# satshakit-nero.net
KiCad netlist of a schematic drawn in EAGLE
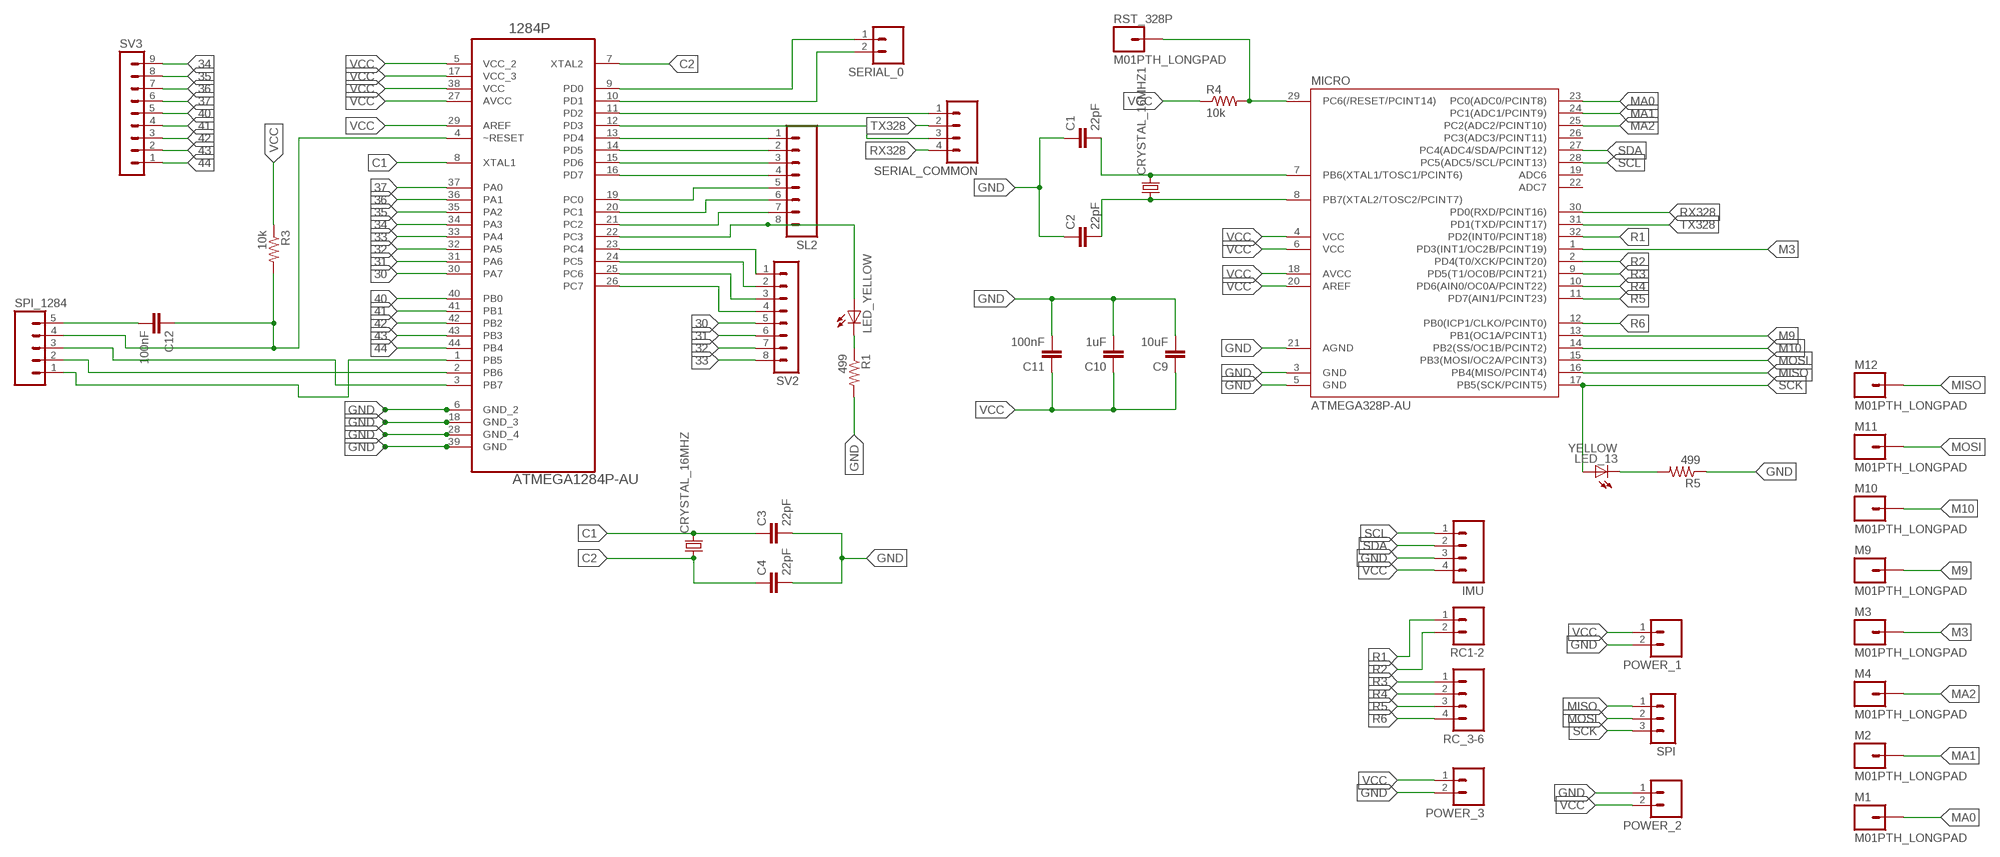
[diagram p0: schematic, sheet 1]

(export (version "E")
  (design (tool "Eeschema 10.0.6"))
  (components
    (comp (ref "1284P")
      (value "ATMEGA1284P-AU")
      (footprint "eagle-import:QFP80P1200X1200X120-44N")
      (libsource (lib "eagle-import") (part "ATMEGA1284P-AU"))
    )
    (comp (ref "C1")
      (value "22pF")
      (footprint "eagle-import:1206")
      (libsource (lib "eagle-import") (part "CAP1206"))
    )
    (comp (ref "C2")
      (value "22pF")
      (footprint "eagle-import:1206")
      (libsource (lib "eagle-import") (part "CAP1206"))
    )
    (comp (ref "C3")
      (value "22pF")
      (footprint "eagle-import:1206")
      (libsource (lib "eagle-import") (part "CAP1206"))
    )
    (comp (ref "C4")
      (value "22pF")
      (footprint "eagle-import:1206")
      (libsource (lib "eagle-import") (part "CAP1206"))
    )
    (comp (ref "C9")
      (value "10uF")
      (footprint "eagle-import:1206")
      (libsource (lib "eagle-import") (part "CAP1206"))
    )
    (comp (ref "C10")
      (value "1uF")
      (footprint "eagle-import:1206")
      (libsource (lib "eagle-import") (part "CAP1206"))
    )
    (comp (ref "C11")
      (value "100nF")
      (footprint "eagle-import:1206")
      (libsource (lib "eagle-import") (part "CAP1206"))
    )
    (comp (ref "C12")
      (value "100nF")
      (footprint "eagle-import:1206")
      (libsource (lib "eagle-import") (part "CAP1206"))
    )
    (comp (ref "CRYSTAL_16MHZ")
      (value "CRYSTALHC49UP")
      (footprint "eagle-import:HC49UP")
      (libsource (lib "eagle-import") (part "CRYSTALHC49UP"))
    )
    (comp (ref "CRYSTAL_16MHZ1")
      (value "CRYSTALHC49UP")
      (footprint "eagle-import:HC49UP")
      (libsource (lib "eagle-import") (part "CRYSTALHC49UP"))
    )
    (comp (ref "IMU")
      (value "M04")
      (footprint "eagle-import:04P")
      (libsource (lib "eagle-import") (part "M04"))
    )
    (comp (ref "LED_13")
      (value "YELLOW")
      (footprint "eagle-import:1206")
      (libsource (lib "eagle-import") (part "LED1206"))
    )
    (comp (ref "LED_YELLOW")
      (value "LED1206")
      (footprint "eagle-import:1206")
      (libsource (lib "eagle-import") (part "FAB_Hello_LED1206"))
    )
    (comp (ref "M1")
      (value "M01PTH_LONGPAD")
      (footprint "eagle-import:1X01_LONGPAD")
      (libsource (lib "eagle-import") (part "M01PTH_LONGPAD"))
    )
    (comp (ref "M2")
      (value "M01PTH_LONGPAD")
      (footprint "eagle-import:1X01_LONGPAD")
      (libsource (lib "eagle-import") (part "M01PTH_LONGPAD"))
    )
    (comp (ref "M3")
      (value "M01PTH_LONGPAD")
      (footprint "eagle-import:1X01_LONGPAD")
      (libsource (lib "eagle-import") (part "M01PTH_LONGPAD"))
    )
    (comp (ref "M4")
      (value "M01PTH_LONGPAD")
      (footprint "eagle-import:1X01_LONGPAD")
      (libsource (lib "eagle-import") (part "M01PTH_LONGPAD"))
    )
    (comp (ref "M9")
      (value "M01PTH_LONGPAD")
      (footprint "eagle-import:1X01_LONGPAD")
      (libsource (lib "eagle-import") (part "M01PTH_LONGPAD"))
    )
    (comp (ref "M10")
      (value "M01PTH_LONGPAD")
      (footprint "eagle-import:1X01_LONGPAD")
      (libsource (lib "eagle-import") (part "M01PTH_LONGPAD"))
    )
    (comp (ref "M11")
      (value "M01PTH_LONGPAD")
      (footprint "eagle-import:1X01_LONGPAD")
      (libsource (lib "eagle-import") (part "M01PTH_LONGPAD"))
    )
    (comp (ref "M12")
      (value "M01PTH_LONGPAD")
      (footprint "eagle-import:1X01_LONGPAD")
      (libsource (lib "eagle-import") (part "M01PTH_LONGPAD"))
    )
    (comp (ref "MICRO")
      (value "ATMEGA328P-AU")
      (footprint "eagle-import:TQFP32-08")
      (libsource (lib "eagle-import") (part "ATMEGA48/88/168-AU"))
    )
    (comp (ref "POWER_1")
      (value "M02")
      (footprint "eagle-import:02P")
      (libsource (lib "eagle-import") (part "M02"))
    )
    (comp (ref "POWER_2")
      (value "M02")
      (footprint "eagle-import:02P")
      (libsource (lib "eagle-import") (part "M02"))
    )
    (comp (ref "POWER_3")
      (value "M02")
      (footprint "eagle-import:02P")
      (libsource (lib "eagle-import") (part "M02"))
    )
    (comp (ref "R1")
      (value "499")
      (footprint "eagle-import:R1206")
      (libsource (lib "eagle-import") (part "RES-US1206"))
    )
    (comp (ref "R3")
      (value "10k")
      (footprint "eagle-import:R1206")
      (libsource (lib "eagle-import") (part "RES-US1206"))
    )
    (comp (ref "R4")
      (value "10k")
      (footprint "eagle-import:1206")
      (libsource (lib "eagle-import") (part "RESISTOR1206"))
    )
    (comp (ref "R5")
      (value "499")
      (footprint "eagle-import:1206")
      (libsource (lib "eagle-import") (part "RESISTOR1206"))
    )
    (comp (ref "RC1-2")
      (value "M02")
      (footprint "eagle-import:02P")
      (libsource (lib "eagle-import") (part "M02"))
    )
    (comp (ref "RC_3-6")
      (value "M04LONGPADS")
      (footprint "eagle-import:1X04_LONGPADS")
      (libsource (lib "eagle-import") (part "M04LONGPADS"))
    )
    (comp (ref "RST_328P")
      (value "M01PTH_LONGPAD")
      (footprint "eagle-import:1X01_LONGPAD")
      (libsource (lib "eagle-import") (part "M01PTH_LONGPAD"))
    )
    (comp (ref "SERIAL_0")
      (value "M02")
      (footprint "eagle-import:02P")
      (libsource (lib "eagle-import") (part "M02"))
    )
    (comp (ref "SERIAL_COMMON")
      (value "M04")
      (footprint "eagle-import:04P")
      (libsource (lib "eagle-import") (part "M04"))
    )
    (comp (ref "SL2")
      (value "M08")
      (footprint "eagle-import:08P")
      (libsource (lib "eagle-import") (part "M08"))
    )
    (comp (ref "SPI")
      (value "MA03-1")
      (footprint "eagle-import:MA03-1")
      (libsource (lib "eagle-import") (part "MA03-1"))
    )
    (comp (ref "SPI_1284")
      (value "M05")
      (footprint "eagle-import:05P")
      (libsource (lib "eagle-import") (part "M05"))
    )
    (comp (ref "SV2")
      (value "MA08-1")
      (footprint "eagle-import:MA08-1")
      (libsource (lib "eagle-import") (part "MA08-1"))
    )
    (comp (ref "SV3")
      (value "MA09-1")
      (footprint "eagle-import:MA09-1")
      (libsource (lib "eagle-import") (part "MA09-1"))
    )
  )
  (nets
    (net (code "1") (name "30") (class "Default")
      (node (ref "1284P") (pin "30") (pinfunction "PA7_30") (pintype "bidirectional"))
      (node (ref "SV2") (pin "5") (pinfunction "5_5") (pintype "passive"))
    )
    (net (code "2") (name "31") (class "Default")
      (node (ref "1284P") (pin "31") (pinfunction "PA6_31") (pintype "bidirectional"))
      (node (ref "SV2") (pin "6") (pinfunction "6_6") (pintype "passive"))
    )
    (net (code "3") (name "32") (class "Default")
      (node (ref "1284P") (pin "32") (pinfunction "PA5_32") (pintype "bidirectional"))
      (node (ref "SV2") (pin "7") (pinfunction "7_7") (pintype "passive"))
    )
    (net (code "4") (name "33") (class "Default")
      (node (ref "1284P") (pin "33") (pinfunction "PA4_33") (pintype "bidirectional"))
      (node (ref "SV2") (pin "8") (pinfunction "8_8") (pintype "passive"))
    )
    (net (code "5") (name "34") (class "Default")
      (node (ref "1284P") (pin "34") (pinfunction "PA3_34") (pintype "bidirectional"))
      (node (ref "SV3") (pin "9") (pinfunction "9_9") (pintype "passive"))
    )
    (net (code "6") (name "35") (class "Default")
      (node (ref "1284P") (pin "35") (pinfunction "PA2_35") (pintype "bidirectional"))
      (node (ref "SV3") (pin "8") (pinfunction "8_8") (pintype "passive"))
    )
    (net (code "7") (name "36") (class "Default")
      (node (ref "1284P") (pin "36") (pinfunction "PA1_36") (pintype "bidirectional"))
      (node (ref "SV3") (pin "7") (pinfunction "7_7") (pintype "passive"))
    )
    (net (code "8") (name "37") (class "Default")
      (node (ref "1284P") (pin "37") (pinfunction "PA0_37") (pintype "bidirectional"))
      (node (ref "SV3") (pin "6") (pinfunction "6_6") (pintype "passive"))
    )
    (net (code "9") (name "40") (class "Default")
      (node (ref "1284P") (pin "40") (pinfunction "PB0_40") (pintype "bidirectional"))
      (node (ref "SV3") (pin "5") (pinfunction "5_5") (pintype "passive"))
    )
    (net (code "10") (name "41") (class "Default")
      (node (ref "1284P") (pin "41") (pinfunction "PB1_41") (pintype "bidirectional"))
      (node (ref "SV3") (pin "4") (pinfunction "4_4") (pintype "passive"))
    )
    (net (code "11") (name "42") (class "Default")
      (node (ref "1284P") (pin "42") (pinfunction "PB2_42") (pintype "bidirectional"))
      (node (ref "SV3") (pin "3") (pinfunction "3_3") (pintype "passive"))
    )
    (net (code "12") (name "43") (class "Default")
      (node (ref "1284P") (pin "43") (pinfunction "PB3_43") (pintype "bidirectional"))
      (node (ref "SV3") (pin "2") (pinfunction "2_2") (pintype "passive"))
    )
    (net (code "13") (name "44") (class "Default")
      (node (ref "1284P") (pin "44") (pinfunction "PB4_44") (pintype "bidirectional"))
      (node (ref "SV3") (pin "1") (pinfunction "1_1") (pintype "passive"))
    )
    (net (code "14") (name "C1") (class "Default")
      (node (ref "1284P") (pin "8") (pinfunction "XTAL1_8") (pintype "input"))
      (node (ref "C3") (pin "1") (pinfunction "1_1") (pintype "passive"))
      (node (ref "CRYSTAL_16MHZ") (pin "2") (pinfunction "2_2") (pintype "passive"))
    )
    (net (code "15") (name "C2") (class "Default")
      (node (ref "1284P") (pin "7") (pinfunction "XTAL2_7") (pintype "output"))
      (node (ref "C4") (pin "1") (pinfunction "1_1") (pintype "passive"))
      (node (ref "CRYSTAL_16MHZ") (pin "1") (pinfunction "1_1") (pintype "passive"))
    )
    (net (code "16") (name "GND") (class "Default")
      (node (ref "1284P") (pin "6") (pinfunction "GND_2_6") (pintype "passive"))
      (node (ref "C1") (pin "1") (pinfunction "1_1") (pintype "passive"))
      (node (ref "C10") (pin "2") (pinfunction "2_2") (pintype "passive"))
      (node (ref "C11") (pin "2") (pinfunction "2_2") (pintype "passive"))
      (node (ref "C2") (pin "1") (pinfunction "1_1") (pintype "passive"))
      (node (ref "C3") (pin "2") (pinfunction "2_2") (pintype "passive"))
      (node (ref "C4") (pin "2") (pinfunction "2_2") (pintype "passive"))
      (node (ref "C9") (pin "2") (pinfunction "2_2") (pintype "passive"))
      (node (ref "IMU") (pin "3") (pinfunction "3_3") (pintype "passive"))
      (node (ref "MICRO") (pin "21") (pinfunction "AGND_21") (pintype "power_in"))
      (node (ref "MICRO") (pin "3") (pinfunction "GND_3") (pintype "power_in"))
      (node (ref "MICRO") (pin "5") (pinfunction "GND_5") (pintype "power_in"))
      (node (ref "POWER_1") (pin "2") (pinfunction "2_2") (pintype "passive"))
      (node (ref "POWER_2") (pin "1") (pinfunction "1_1") (pintype "passive"))
      (node (ref "POWER_3") (pin "2") (pinfunction "2_2") (pintype "passive"))
      (node (ref "R1") (pin "2") (pinfunction "2_2") (pintype "passive"))
      (node (ref "R5") (pin "1") (pinfunction "1_1") (pintype "passive"))
    )
    (net (code "17") (name "M3") (class "Default")
      (node (ref "M3") (pin "1") (pinfunction "1_1") (pintype "passive"))
      (node (ref "MICRO") (pin "1") (pinfunction "PD3(INT1/OC2B/PCINT19)_1") (pintype "bidirectional"))
    )
    (net (code "18") (name "M9") (class "Default")
      (node (ref "M9") (pin "1") (pinfunction "1_1") (pintype "passive"))
      (node (ref "MICRO") (pin "13") (pinfunction "PB1(OC1A/PCINT1)_13") (pintype "bidirectional"))
    )
    (net (code "19") (name "M10") (class "Default")
      (node (ref "M10") (pin "1") (pinfunction "1_1") (pintype "passive"))
      (node (ref "MICRO") (pin "14") (pinfunction "PB2(SS/OC1B/PCINT2)_14") (pintype "bidirectional"))
    )
    (net (code "20") (name "MA0") (class "Default")
      (node (ref "M1") (pin "1") (pinfunction "1_1") (pintype "passive"))
      (node (ref "MICRO") (pin "23") (pinfunction "PC0(ADC0/PCINT8)_23") (pintype "bidirectional"))
    )
    (net (code "21") (name "MA1") (class "Default")
      (node (ref "M2") (pin "1") (pinfunction "1_1") (pintype "passive"))
      (node (ref "MICRO") (pin "24") (pinfunction "PC1(ADC1/PCINT9)_24") (pintype "bidirectional"))
    )
    (net (code "22") (name "MA2") (class "Default")
      (node (ref "M4") (pin "1") (pinfunction "1_1") (pintype "passive"))
      (node (ref "MICRO") (pin "25") (pinfunction "PC2(ADC2/PCINT10)_25") (pintype "bidirectional"))
    )
    (net (code "23") (name "MISO") (class "Default")
      (node (ref "M12") (pin "1") (pinfunction "1_1") (pintype "passive"))
      (node (ref "MICRO") (pin "16") (pinfunction "PB4(MISO/PCINT4)_16") (pintype "bidirectional"))
      (node (ref "SPI") (pin "1") (pinfunction "1_1") (pintype "passive"))
    )
    (net (code "24") (name "MOSI") (class "Default")
      (node (ref "M11") (pin "1") (pinfunction "1_1") (pintype "passive"))
      (node (ref "MICRO") (pin "15") (pinfunction "PB3(MOSI/OC2A/PCINT3)_15") (pintype "bidirectional"))
      (node (ref "SPI") (pin "2") (pinfunction "2_2") (pintype "passive"))
    )
    (net (code "25") (name "Net-(1284P-PB5)") (class "Default")
      (node (ref "1284P") (pin "1") (pinfunction "PB5_1") (pintype "bidirectional"))
      (node (ref "SPI_1284") (pin "1") (pinfunction "1_1") (pintype "passive"))
    )
    (net (code "26") (name "Net-(1284P-PB6)") (class "Default")
      (node (ref "1284P") (pin "2") (pinfunction "PB6_2") (pintype "bidirectional"))
      (node (ref "SPI_1284") (pin "2") (pinfunction "2_2") (pintype "passive"))
    )
    (net (code "27") (name "Net-(1284P-PB7)") (class "Default")
      (node (ref "1284P") (pin "3") (pinfunction "PB7_3") (pintype "bidirectional"))
      (node (ref "SPI_1284") (pin "3") (pinfunction "3_3") (pintype "passive"))
    )
    (net (code "28") (name "Net-(1284P-PC0)") (class "Default")
      (node (ref "1284P") (pin "19") (pinfunction "PC0_19") (pintype "bidirectional"))
      (node (ref "SL2") (pin "5") (pinfunction "5_5") (pintype "passive"))
    )
    (net (code "29") (name "Net-(1284P-PC1)") (class "Default")
      (node (ref "1284P") (pin "20") (pinfunction "PC1_20") (pintype "bidirectional"))
      (node (ref "SL2") (pin "6") (pinfunction "6_6") (pintype "passive"))
    )
    (net (code "30") (name "Net-(1284P-PC2)") (class "Default")
      (node (ref "1284P") (pin "21") (pinfunction "PC2_21") (pintype "bidirectional"))
      (node (ref "SL2") (pin "7") (pinfunction "7_7") (pintype "passive"))
    )
    (net (code "31") (name "Net-(1284P-PC3)") (class "Default")
      (node (ref "1284P") (pin "22") (pinfunction "PC3_22") (pintype "bidirectional"))
      (node (ref "LED_YELLOW") (pin "1") (pinfunction "A_1") (pintype "passive"))
      (node (ref "SL2") (pin "8") (pinfunction "8_8") (pintype "passive"))
    )
    (net (code "32") (name "Net-(1284P-PC4)") (class "Default")
      (node (ref "1284P") (pin "23") (pinfunction "PC4_23") (pintype "bidirectional"))
      (node (ref "SV2") (pin "1") (pinfunction "1_1") (pintype "passive"))
    )
    (net (code "33") (name "Net-(1284P-PC5)") (class "Default")
      (node (ref "1284P") (pin "24") (pinfunction "PC5_24") (pintype "bidirectional"))
      (node (ref "SV2") (pin "2") (pinfunction "2_2") (pintype "passive"))
    )
    (net (code "34") (name "Net-(1284P-PC6)") (class "Default")
      (node (ref "1284P") (pin "25") (pinfunction "PC6_25") (pintype "bidirectional"))
      (node (ref "SV2") (pin "3") (pinfunction "3_3") (pintype "passive"))
    )
    (net (code "35") (name "Net-(1284P-PC7)") (class "Default")
      (node (ref "1284P") (pin "26") (pinfunction "PC7_26") (pintype "bidirectional"))
      (node (ref "SV2") (pin "4") (pinfunction "4_4") (pintype "passive"))
    )
    (net (code "36") (name "Net-(1284P-PD0)") (class "Default")
      (node (ref "1284P") (pin "9") (pinfunction "PD0_9") (pintype "bidirectional"))
      (node (ref "SERIAL_0") (pin "1") (pinfunction "1_1") (pintype "passive"))
    )
    (net (code "37") (name "Net-(1284P-PD1)") (class "Default")
      (node (ref "1284P") (pin "10") (pinfunction "PD1_10") (pintype "bidirectional"))
      (node (ref "SERIAL_0") (pin "2") (pinfunction "2_2") (pintype "passive"))
    )
    (net (code "38") (name "Net-(1284P-PD2)") (class "Default")
      (node (ref "1284P") (pin "11") (pinfunction "PD2_11") (pintype "bidirectional"))
      (node (ref "SERIAL_COMMON") (pin "1") (pinfunction "1_1") (pintype "passive"))
    )
    (net (code "39") (name "Net-(1284P-PD3)") (class "Default")
      (node (ref "1284P") (pin "12") (pinfunction "PD3_12") (pintype "bidirectional"))
      (node (ref "SERIAL_COMMON") (pin "3") (pinfunction "3_3") (pintype "passive"))
    )
    (net (code "40") (name "Net-(1284P-PD4)") (class "Default")
      (node (ref "1284P") (pin "13") (pinfunction "PD4_13") (pintype "bidirectional"))
      (node (ref "SL2") (pin "1") (pinfunction "1_1") (pintype "passive"))
    )
    (net (code "41") (name "Net-(1284P-PD5)") (class "Default")
      (node (ref "1284P") (pin "14") (pinfunction "PD5_14") (pintype "bidirectional"))
      (node (ref "SL2") (pin "2") (pinfunction "2_2") (pintype "passive"))
    )
    (net (code "42") (name "Net-(1284P-PD6)") (class "Default")
      (node (ref "1284P") (pin "15") (pinfunction "PD6_15") (pintype "bidirectional"))
      (node (ref "SL2") (pin "3") (pinfunction "3_3") (pintype "passive"))
    )
    (net (code "43") (name "Net-(1284P-PD7)") (class "Default")
      (node (ref "1284P") (pin "16") (pinfunction "PD7_16") (pintype "bidirectional"))
      (node (ref "SL2") (pin "4") (pinfunction "4_4") (pintype "passive"))
    )
    (net (code "44") (name "Net-(1284P-~{RESET})") (class "Default")
      (node (ref "1284P") (pin "4") (pinfunction "~{RESET}_4") (pintype "input"))
      (node (ref "C12") (pin "1") (pinfunction "1_1") (pintype "passive"))
      (node (ref "R3") (pin "2") (pinfunction "2_2") (pintype "passive"))
      (node (ref "SPI_1284") (pin "4") (pinfunction "4_4") (pintype "passive"))
    )
    (net (code "45") (name "Net-(C12-Pad2)") (class "Default")
      (node (ref "C12") (pin "2") (pinfunction "2_2") (pintype "passive"))
      (node (ref "SPI_1284") (pin "5") (pinfunction "5_5") (pintype "passive"))
    )
    (net (code "46") (name "Net-(LED_13-C)") (class "Default")
      (node (ref "LED_13") (pin "2") (pinfunction "C_2") (pintype "passive"))
      (node (ref "R5") (pin "2") (pinfunction "2_2") (pintype "passive"))
    )
    (net (code "47") (name "Net-(LED_YELLOW-C)") (class "Default")
      (node (ref "LED_YELLOW") (pin "2") (pinfunction "C_2") (pintype "passive"))
      (node (ref "R1") (pin "1") (pinfunction "1_1") (pintype "passive"))
    )
    (net (code "48") (name "Net-(MICRO-PB6(XTAL1{slash}TOSC1{slash}PCINT6))") (class "Default")
      (node (ref "C1") (pin "2") (pinfunction "2_2") (pintype "passive"))
      (node (ref "CRYSTAL_16MHZ1") (pin "2") (pinfunction "2_2") (pintype "passive"))
      (node (ref "MICRO") (pin "7") (pinfunction "PB6(XTAL1/TOSC1/PCINT6)_7") (pintype "bidirectional"))
    )
    (net (code "49") (name "Net-(MICRO-PB7(XTAL2{slash}TOSC2{slash}PCINT7))") (class "Default")
      (node (ref "C2") (pin "2") (pinfunction "2_2") (pintype "passive"))
      (node (ref "CRYSTAL_16MHZ1") (pin "1") (pinfunction "1_1") (pintype "passive"))
      (node (ref "MICRO") (pin "8") (pinfunction "PB7(XTAL2/TOSC2/PCINT7)_8") (pintype "bidirectional"))
    )
    (net (code "50") (name "Net-(MICRO-PC6({slash}RESET{slash}PCINT14))") (class "Default")
      (node (ref "MICRO") (pin "29") (pinfunction "PC6(/RESET/PCINT14)_29") (pintype "bidirectional"))
      (node (ref "R4") (pin "2") (pinfunction "2_2") (pintype "passive"))
      (node (ref "RST_328P") (pin "1") (pinfunction "1_1") (pintype "passive"))
    )
    (net (code "51") (name "R1") (class "Default")
      (node (ref "MICRO") (pin "32") (pinfunction "PD2(INT0/PCINT18)_32") (pintype "bidirectional"))
      (node (ref "RC1-2") (pin "1") (pinfunction "1_1") (pintype "passive"))
    )
    (net (code "52") (name "R2") (class "Default")
      (node (ref "MICRO") (pin "2") (pinfunction "PD4(T0/XCK/PCINT20)_2") (pintype "bidirectional"))
      (node (ref "RC1-2") (pin "2") (pinfunction "2_2") (pintype "passive"))
    )
    (net (code "53") (name "R3") (class "Default")
      (node (ref "MICRO") (pin "9") (pinfunction "PD5(T1/OC0B/PCINT21)_9") (pintype "bidirectional"))
      (node (ref "RC_3-6") (pin "1") (pinfunction "1_1") (pintype "passive"))
    )
    (net (code "54") (name "R4") (class "Default")
      (node (ref "MICRO") (pin "10") (pinfunction "PD6(AIN0/OC0A/PCINT22)_10") (pintype "bidirectional"))
      (node (ref "RC_3-6") (pin "2") (pinfunction "2_2") (pintype "passive"))
    )
    (net (code "55") (name "R5") (class "Default")
      (node (ref "MICRO") (pin "11") (pinfunction "PD7(AIN1/PCINT23)_11") (pintype "bidirectional"))
      (node (ref "RC_3-6") (pin "3") (pinfunction "3_3") (pintype "passive"))
    )
    (net (code "56") (name "R6") (class "Default")
      (node (ref "MICRO") (pin "12") (pinfunction "PB0(ICP1/CLKO/PCINT0)_12") (pintype "bidirectional"))
      (node (ref "RC_3-6") (pin "4") (pinfunction "4_4") (pintype "passive"))
    )
    (net (code "57") (name "RX328") (class "Default")
      (node (ref "MICRO") (pin "30") (pinfunction "PD0(RXD/PCINT16)_30") (pintype "bidirectional"))
      (node (ref "SERIAL_COMMON") (pin "4") (pinfunction "4_4") (pintype "passive"))
    )
    (net (code "58") (name "SCK") (class "Default")
      (node (ref "LED_13") (pin "1") (pinfunction "A_1") (pintype "passive"))
      (node (ref "MICRO") (pin "17") (pinfunction "PB5(SCK/PCINT5)_17") (pintype "bidirectional"))
      (node (ref "SPI") (pin "3") (pinfunction "3_3") (pintype "passive"))
    )
    (net (code "59") (name "SCL") (class "Default")
      (node (ref "IMU") (pin "1") (pinfunction "1_1") (pintype "passive"))
      (node (ref "MICRO") (pin "28") (pinfunction "PC5(ADC5/SCL/PCINT13)_28") (pintype "bidirectional"))
    )
    (net (code "60") (name "SDA") (class "Default")
      (node (ref "IMU") (pin "2") (pinfunction "2_2") (pintype "passive"))
      (node (ref "MICRO") (pin "27") (pinfunction "PC4(ADC4/SDA/PCINT12)_27") (pintype "bidirectional"))
    )
    (net (code "61") (name "TX328") (class "Default")
      (node (ref "MICRO") (pin "31") (pinfunction "PD1(TXD/PCINT17)_31") (pintype "bidirectional"))
      (node (ref "SERIAL_COMMON") (pin "2") (pinfunction "2_2") (pintype "passive"))
    )
    (net (code "62") (name "VCC") (class "Default")
      (node (ref "1284P") (pin "17") (pinfunction "VCC_3_17") (pintype "power_in"))
      (node (ref "1284P") (pin "27") (pinfunction "AVCC_27") (pintype "power_in"))
      (node (ref "1284P") (pin "29") (pinfunction "AREF_29") (pintype "input"))
      (node (ref "1284P") (pin "5") (pinfunction "VCC_2_5") (pintype "power_in"))
      (node (ref "C10") (pin "1") (pinfunction "1_1") (pintype "passive"))
      (node (ref "C11") (pin "1") (pinfunction "1_1") (pintype "passive"))
      (node (ref "C9") (pin "1") (pinfunction "1_1") (pintype "passive"))
      (node (ref "IMU") (pin "4") (pinfunction "4_4") (pintype "passive"))
      (node (ref "MICRO") (pin "18") (pinfunction "AVCC_18") (pintype "passive"))
      (node (ref "MICRO") (pin "20") (pinfunction "AREF_20") (pintype "passive"))
      (node (ref "MICRO") (pin "4") (pinfunction "VCC_4") (pintype "power_in"))
      (node (ref "MICRO") (pin "6") (pinfunction "VCC_6") (pintype "power_in"))
      (node (ref "POWER_1") (pin "1") (pinfunction "1_1") (pintype "passive"))
      (node (ref "POWER_2") (pin "2") (pinfunction "2_2") (pintype "passive"))
      (node (ref "POWER_3") (pin "1") (pinfunction "1_1") (pintype "passive"))
      (node (ref "R3") (pin "1") (pinfunction "1_1") (pintype "passive"))
      (node (ref "R4") (pin "1") (pinfunction "1_1") (pintype "passive"))
    )
    (net (code "63") (name "unconnected-(1284P-GND-Pad39)") (class "Default")
      (node (ref "1284P") (pin "39") (pinfunction "GND_39") (pintype "passive"))
    )
    (net (code "64") (name "unconnected-(1284P-GND_3-Pad18)") (class "Default")
      (node (ref "1284P") (pin "18") (pinfunction "GND_3_18") (pintype "passive"))
    )
    (net (code "65") (name "unconnected-(1284P-GND_4-Pad28)") (class "Default")
      (node (ref "1284P") (pin "28") (pinfunction "GND_4_28") (pintype "passive"))
    )
    (net (code "66") (name "unconnected-(1284P-VCC-Pad38)") (class "Default")
      (node (ref "1284P") (pin "38") (pinfunction "VCC_38") (pintype "power_in"))
    )
    (net (code "67") (name "unconnected-(MICRO-ADC6-Pad19)") (class "Default")
      (node (ref "MICRO") (pin "19") (pinfunction "ADC6_19") (pintype "passive"))
    )
    (net (code "68") (name "unconnected-(MICRO-ADC7-Pad22)") (class "Default")
      (node (ref "MICRO") (pin "22") (pinfunction "ADC7_22") (pintype "passive"))
    )
    (net (code "69") (name "unconnected-(MICRO-PC3(ADC3{slash}PCINT11)-Pad26)") (class "Default")
      (node (ref "MICRO") (pin "26") (pinfunction "PC3(ADC3/PCINT11)_26") (pintype "bidirectional"))
    )
  )
)
